# Stepper_motor.net
KiCad netlist of a schematic drawn in EAGLE
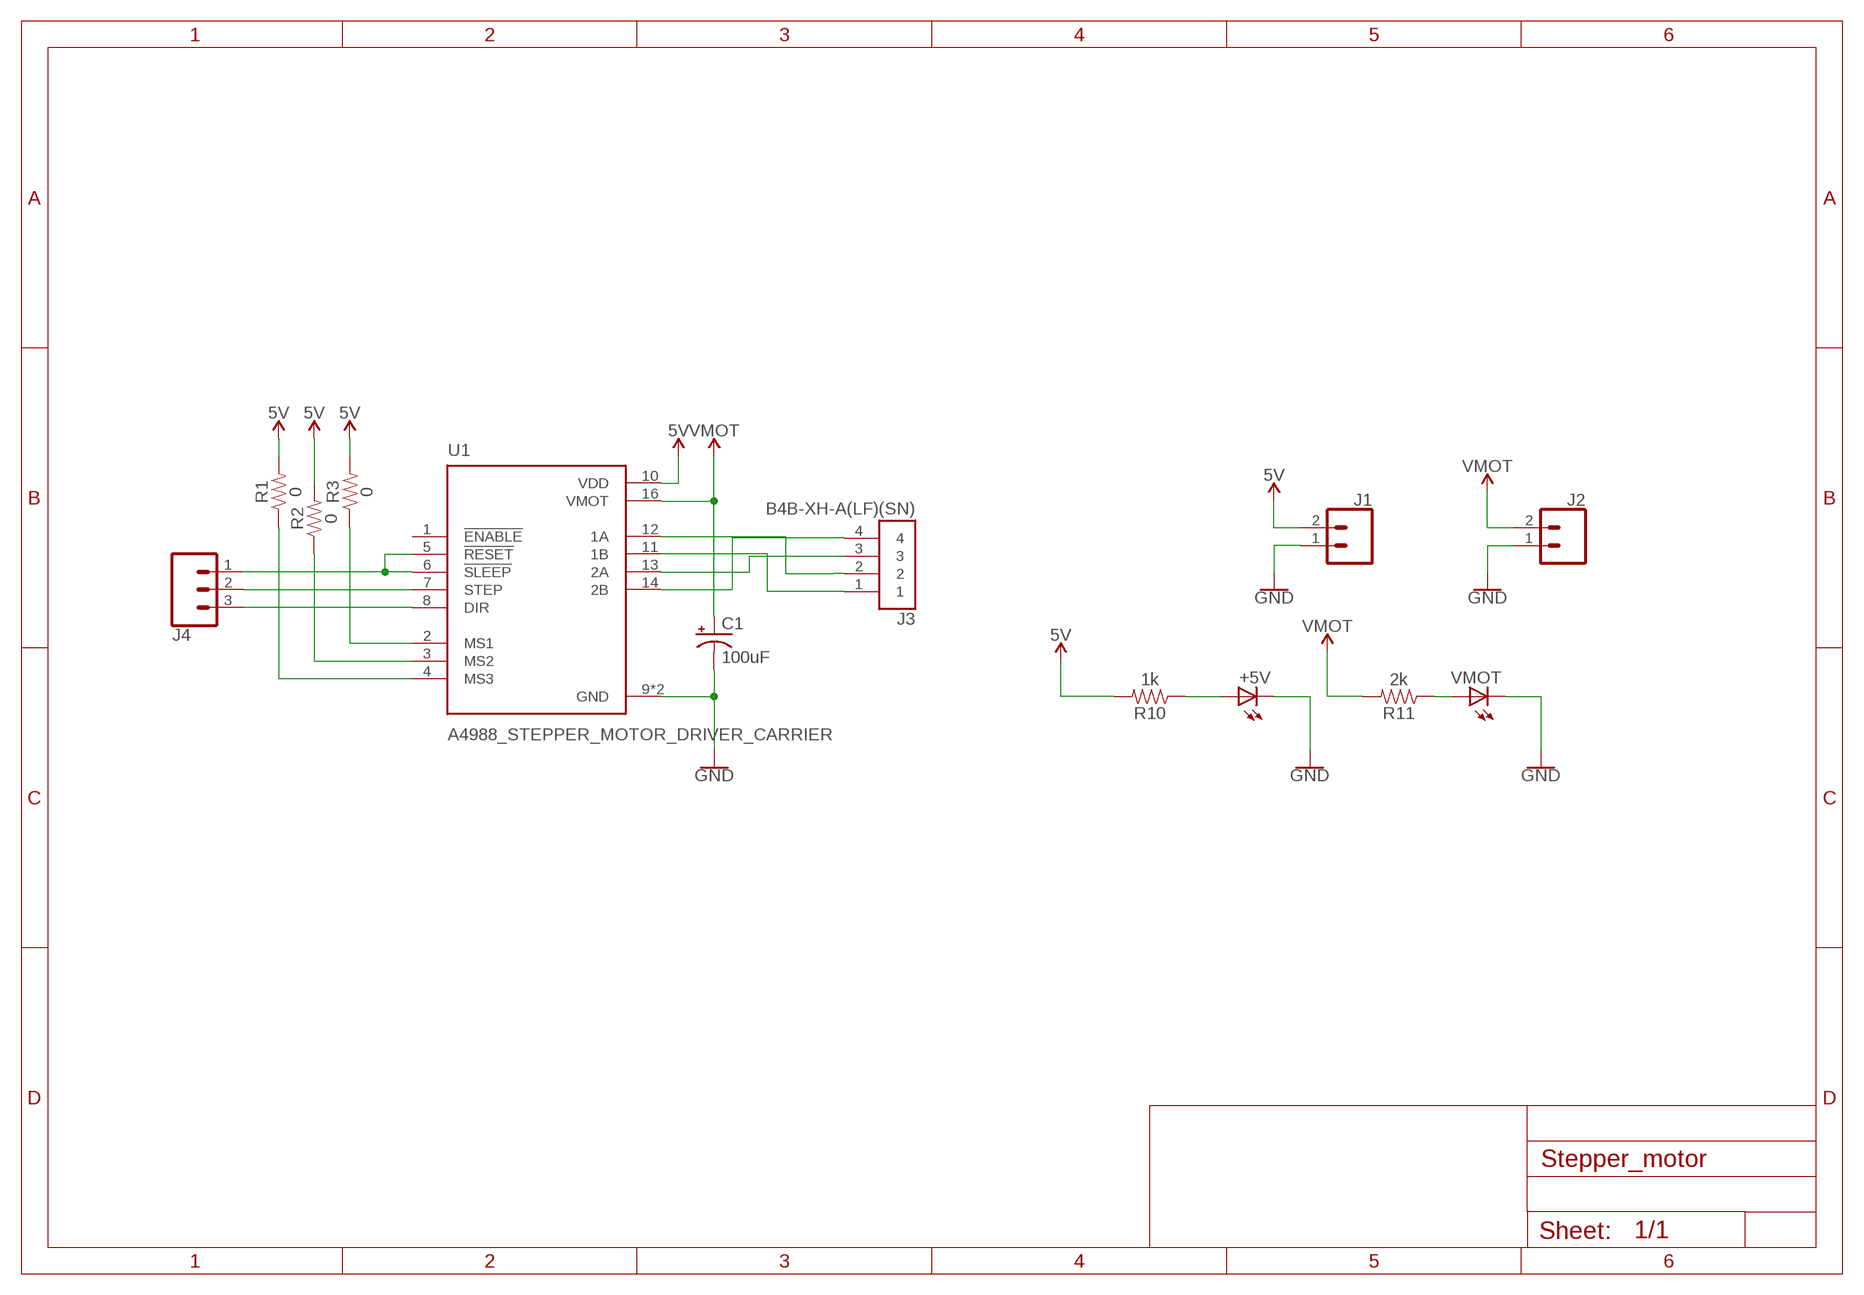
[diagram p0: schematic, sheet 1]

(export (version "E")
  (design (tool "Eeschema 10.0.6"))
  (components
    (comp (ref "+5V")
      (value "LEDP-LCC-2")
      (footprint "eagle-import:P-LCC-2")
      (libsource (lib "eagle-import") (part "LEDP-LCC-2"))
    )
    (comp (ref "C1")
      (value "100uF")
      (footprint "eagle-import:PANASONIC_D")
      (libsource (lib "eagle-import") (part "100UF-POLAR-25V-20%(ELEC)"))
    )
    (comp (ref "J1")
      (value "CONN_025MM")
      (footprint "eagle-import:SCREWTERMINAL-5MM-2")
      (libsource (lib "eagle-import") (part "CONN_025MM"))
    )
    (comp (ref "J2")
      (value "CONN_025MM")
      (footprint "eagle-import:SCREWTERMINAL-5MM-2")
      (libsource (lib "eagle-import") (part "CONN_025MM"))
    )
    (comp (ref "J3")
      (value "B4B-XH-A(LF)(SN)")
      (footprint "eagle-import:JST_B4B-XH-A(LF)(SN)")
      (fields (field (name "MF") "JST Sales"))
      (libsource (lib "eagle-import") (part "B4B-XH-A(LF)(SN)"))
    )
    (comp (ref "J4")
      (value "CONN_03SCREW")
      (footprint "eagle-import:SCREWTERMINAL-3.5MM-3")
      (libsource (lib "eagle-import") (part "CONN_03SCREW"))
    )
    (comp (ref "R1")
      (value "0")
      (footprint "eagle-import:1206")
      (libsource (lib "eagle-import") (part "RESISTOR1206"))
    )
    (comp (ref "R2")
      (value "0")
      (footprint "eagle-import:1206")
      (libsource (lib "eagle-import") (part "RESISTOR1206"))
    )
    (comp (ref "R3")
      (value "0")
      (footprint "eagle-import:1206")
      (libsource (lib "eagle-import") (part "RESISTOR1206"))
    )
    (comp (ref "R10")
      (value "1k")
      (footprint "eagle-import:1206")
      (libsource (lib "eagle-import") (part "RESISTOR1206"))
    )
    (comp (ref "R11")
      (value "2k")
      (footprint "eagle-import:1206")
      (libsource (lib "eagle-import") (part "RESISTOR1206"))
    )
    (comp (ref "U1")
      (value "A4988_STEPPER_MOTOR_DRIVER_CARRIER")
      (footprint "eagle-import:MODULE_A4988_STEPPER_MOTOR_DRIVER_CARRIER")
      (fields (field (name "MF") "Pololu") (field (name "MP") "A4988 STEPPER MOTOR DRIVER CARRIER"))
      (libsource (lib "eagle-import") (part "A4988_STEPPER_MOTOR_DRIVER_CARRIER"))
    )
    (comp (ref "VMOT")
      (value "LEDP-LCC-2")
      (footprint "eagle-import:P-LCC-2")
      (libsource (lib "eagle-import") (part "LEDP-LCC-2"))
    )
  )
  (nets
    (net (code "1") (name "5V") (class "Default")
      (node (ref "J1") (pin "2") (pinfunction "2_2") (pintype "passive"))
      (node (ref "R1") (pin "2") (pinfunction "2_2") (pintype "passive"))
      (node (ref "R10") (pin "2") (pinfunction "2_2") (pintype "passive"))
      (node (ref "R2") (pin "2") (pinfunction "2_2") (pintype "passive"))
      (node (ref "R3") (pin "2") (pinfunction "2_2") (pintype "passive"))
      (node (ref "U1") (pin "10") (pinfunction "VDD_10") (pintype "power_in"))
    )
    (net (code "2") (name "GND") (class "Default")
      (node (ref "+5V") (pin "C") (pinfunction "C_C") (pintype "passive"))
      (node (ref "C1") (pin "-") (pinfunction "-_-") (pintype "passive"))
      (node (ref "J1") (pin "1") (pinfunction "1_1") (pintype "passive"))
      (node (ref "J2") (pin "1") (pinfunction "1_1") (pintype "passive"))
      (node (ref "U1") (pin "15") (pinfunction "GND_15") (pintype "power_in"))
      (node (ref "U1") (pin "9") (pinfunction "GND_9") (pintype "power_in"))
      (node (ref "VMOT") (pin "C") (pinfunction "C_C") (pintype "passive"))
    )
    (net (code "3") (name "Net-(+5V-PadA)") (class "Default")
      (node (ref "+5V") (pin "A") (pinfunction "A_A") (pintype "passive"))
      (node (ref "R10") (pin "1") (pinfunction "1_1") (pintype "passive"))
    )
    (net (code "4") (name "Net-(R11-Pad1)") (class "Default")
      (node (ref "R11") (pin "1") (pinfunction "1_1") (pintype "passive"))
      (node (ref "VMOT") (pin "A") (pinfunction "A_A") (pintype "passive"))
    )
    (net (code "5") (name "Net-(U1-1A)") (class "Default")
      (node (ref "J3") (pin "2") (pinfunction "2_2") (pintype "passive"))
      (node (ref "U1") (pin "12") (pinfunction "1A_12") (pintype "output"))
    )
    (net (code "6") (name "Net-(U1-1B)") (class "Default")
      (node (ref "J3") (pin "1") (pinfunction "1_1") (pintype "passive"))
      (node (ref "U1") (pin "11") (pinfunction "1B_11") (pintype "output"))
    )
    (net (code "7") (name "Net-(U1-2A)") (class "Default")
      (node (ref "J3") (pin "3") (pinfunction "3_3") (pintype "passive"))
      (node (ref "U1") (pin "13") (pinfunction "2A_13") (pintype "output"))
    )
    (net (code "8") (name "Net-(U1-2B)") (class "Default")
      (node (ref "J3") (pin "4") (pinfunction "4_4") (pintype "passive"))
      (node (ref "U1") (pin "14") (pinfunction "2B_14") (pintype "output"))
    )
    (net (code "9") (name "Net-(U1-DIR)") (class "Default")
      (node (ref "J4") (pin "3") (pinfunction "3_3") (pintype "passive"))
      (node (ref "U1") (pin "8") (pinfunction "DIR_8") (pintype "input"))
    )
    (net (code "10") (name "Net-(U1-MS1)") (class "Default")
      (node (ref "R3") (pin "1") (pinfunction "1_1") (pintype "passive"))
      (node (ref "U1") (pin "2") (pinfunction "MS1_2") (pintype "input"))
    )
    (net (code "11") (name "Net-(U1-MS2)") (class "Default")
      (node (ref "R2") (pin "1") (pinfunction "1_1") (pintype "passive"))
      (node (ref "U1") (pin "3") (pinfunction "MS2_3") (pintype "input"))
    )
    (net (code "12") (name "Net-(U1-MS3)") (class "Default")
      (node (ref "R1") (pin "1") (pinfunction "1_1") (pintype "passive"))
      (node (ref "U1") (pin "4") (pinfunction "MS3_4") (pintype "input"))
    )
    (net (code "13") (name "Net-(U1-STEP)") (class "Default")
      (node (ref "J4") (pin "2") (pinfunction "2_2") (pintype "passive"))
      (node (ref "U1") (pin "7") (pinfunction "STEP_7") (pintype "input"))
    )
    (net (code "14") (name "Net-(U1-~{RESET})") (class "Default")
      (node (ref "J4") (pin "1") (pinfunction "1_1") (pintype "passive"))
      (node (ref "U1") (pin "5") (pinfunction "~{RESET}_5") (pintype "input"))
      (node (ref "U1") (pin "6") (pinfunction "~{SLEEP}_6") (pintype "input"))
    )
    (net (code "15") (name "VMOT") (class "Default")
      (node (ref "C1") (pin "+") (pinfunction "+_+") (pintype "passive"))
      (node (ref "J2") (pin "2") (pinfunction "2_2") (pintype "passive"))
      (node (ref "R11") (pin "2") (pinfunction "2_2") (pintype "passive"))
      (node (ref "U1") (pin "16") (pinfunction "VMOT_16") (pintype "power_in"))
    )
    (net (code "16") (name "unconnected-(U1-~{ENABLE}-Pad1)") (class "Default")
      (node (ref "U1") (pin "1") (pinfunction "~{ENABLE}_1") (pintype "input"))
    )
  )
)
